# 328_ch340g_testas.net
KiCad netlist of a schematic drawn in EAGLE
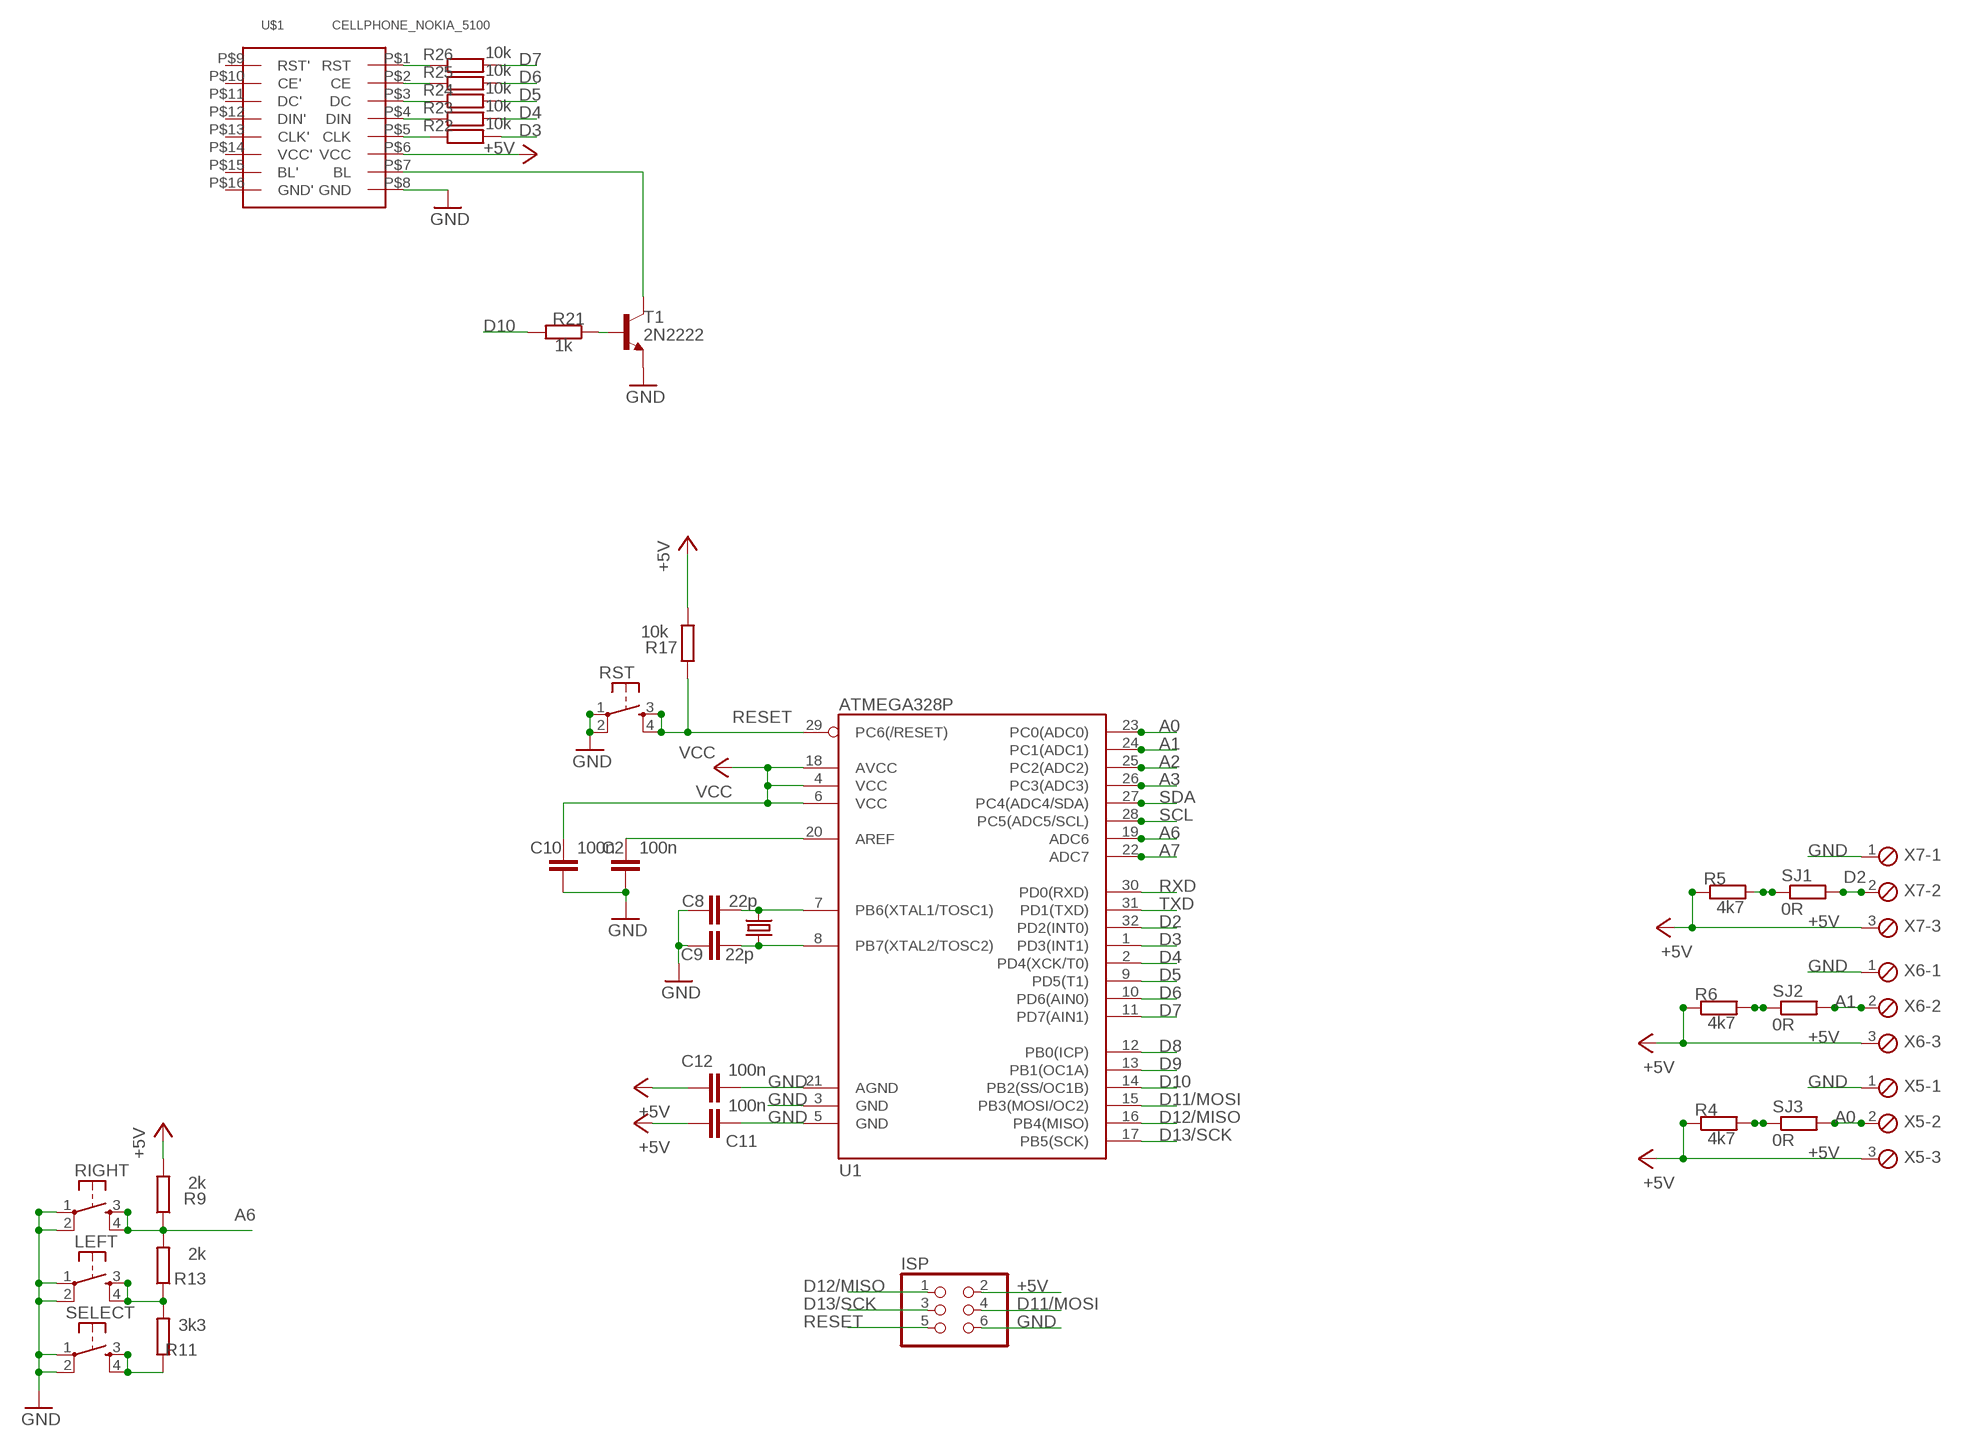
[diagram p0: schematic, sheet 1]

(export (version "E")
  (design (tool "Eeschema 10.0.6"))
  (components
    (comp (ref "C2")
      (value "100n")
      (footprint "eagle-import:C0805")
      (libsource (lib "eagle-import") (part "C-EUC0805"))
    )
    (comp (ref "C8")
      (value "22p")
      (footprint "eagle-import:C0805")
      (libsource (lib "eagle-import") (part "C-EUC0805"))
    )
    (comp (ref "C9")
      (value "22p")
      (footprint "eagle-import:C0805")
      (libsource (lib "eagle-import") (part "C-EUC0805"))
    )
    (comp (ref "C10")
      (value "100n")
      (footprint "eagle-import:C0805")
      (libsource (lib "eagle-import") (part "C-EUC0805"))
    )
    (comp (ref "C11")
      (value "100n")
      (footprint "eagle-import:C0805")
      (libsource (lib "eagle-import") (part "C-EUC0805"))
    )
    (comp (ref "C12")
      (value "100n")
      (footprint "eagle-import:C0805")
      (libsource (lib "eagle-import") (part "C-EUC0805"))
    )
    (comp (ref "ISP")
      (value "PINHD-2X3")
      (footprint "eagle-import:2X03")
      (libsource (lib "eagle-import") (part "PINHD-2X3"))
    )
    (comp (ref "LEFT")
      (value "TAC_SWITCHPTH")
      (footprint "eagle-import:TACTILE-PTH")
      (libsource (lib "eagle-import") (part "TAC_SWITCHPTH"))
    )
    (comp (ref "R4")
      (value "4k7")
      (footprint "eagle-import:R0805")
      (libsource (lib "eagle-import") (part "R-EU_R0805"))
    )
    (comp (ref "R5")
      (value "4k7")
      (footprint "eagle-import:R0805")
      (libsource (lib "eagle-import") (part "R-EU_R0805"))
    )
    (comp (ref "R6")
      (value "4k7")
      (footprint "eagle-import:R0805")
      (libsource (lib "eagle-import") (part "R-EU_R0805"))
    )
    (comp (ref "R9")
      (value "2k")
      (footprint "eagle-import:R0805")
      (libsource (lib "eagle-import") (part "R-EU_R0805"))
    )
    (comp (ref "R11")
      (value "3k3")
      (footprint "eagle-import:R0805")
      (libsource (lib "eagle-import") (part "R-EU_R0805"))
    )
    (comp (ref "R13")
      (value "2k")
      (footprint "eagle-import:R0805")
      (libsource (lib "eagle-import") (part "R-EU_R0805"))
    )
    (comp (ref "R17")
      (value "10k")
      (footprint "eagle-import:R0805")
      (libsource (lib "eagle-import") (part "R-EU_R0805"))
    )
    (comp (ref "R21")
      (value "1k")
      (footprint "eagle-import:R0805")
      (libsource (lib "eagle-import") (part "R-EU_R0805"))
    )
    (comp (ref "R22")
      (value "10k")
      (footprint "eagle-import:R0805")
      (libsource (lib "eagle-import") (part "R-EU_R0805"))
    )
    (comp (ref "R23")
      (value "10k")
      (footprint "eagle-import:R0805")
      (libsource (lib "eagle-import") (part "R-EU_R0805"))
    )
    (comp (ref "R24")
      (value "10k")
      (footprint "eagle-import:R0805")
      (libsource (lib "eagle-import") (part "R-EU_R0805"))
    )
    (comp (ref "R25")
      (value "10k")
      (footprint "eagle-import:R0805")
      (libsource (lib "eagle-import") (part "R-EU_R0805"))
    )
    (comp (ref "R26")
      (value "10k")
      (footprint "eagle-import:R0805")
      (libsource (lib "eagle-import") (part "R-EU_R0805"))
    )
    (comp (ref "RIGHT")
      (value "TAC_SWITCHPTH")
      (footprint "eagle-import:TACTILE-PTH")
      (libsource (lib "eagle-import") (part "TAC_SWITCHPTH"))
    )
    (comp (ref "RST")
      (value "TAC_SWITCHPTH")
      (footprint "eagle-import:TACTILE-PTH")
      (libsource (lib "eagle-import") (part "TAC_SWITCHPTH"))
    )
    (comp (ref "SELECT")
      (value "TAC_SWITCHPTH")
      (footprint "eagle-import:TACTILE-PTH")
      (libsource (lib "eagle-import") (part "TAC_SWITCHPTH"))
    )
    (comp (ref "SJ1")
      (value "0R")
      (footprint "eagle-import:R0402")
      (libsource (lib "eagle-import") (part "R-EU_R0402"))
    )
    (comp (ref "SJ2")
      (value "0R")
      (footprint "eagle-import:R0402")
      (libsource (lib "eagle-import") (part "R-EU_R0402"))
    )
    (comp (ref "SJ3")
      (value "0R")
      (footprint "eagle-import:R0402")
      (libsource (lib "eagle-import") (part "R-EU_R0402"))
    )
    (comp (ref "T1")
      (value "2N2222")
      (footprint "eagle-import:TO92-EBC-OVAL")
      (libsource (lib "eagle-import") (part "2N2222"))
    )
    (comp (ref "U$1")
      (value "CELLPHONE_NOKIA_5100")
      (footprint "eagle-import:CELLPHONE_NOKIA_5100_SPARKFUN")
      (libsource (lib "eagle-import") (part "CELLPHONE_NOKIA_5100"))
    )
    (comp (ref "U1")
      (value "ATMEGA328P")
      (footprint "eagle-import:TQFP32-08")
      (libsource (lib "eagle-import") (part "ATMEGA328_SMT"))
    )
    (comp (ref "X2")
      (value "16MHz")
      (footprint "eagle-import:HC49US")
      (libsource (lib "eagle-import") (part "CRYSTALHC49US"))
    )
    (comp (ref "X5")
      (value "MPT3")
      (footprint "eagle-import:3POL254")
      (libsource (lib "eagle-import") (part "MPT3"))
    )
    (comp (ref "X6")
      (value "MPT3")
      (footprint "eagle-import:3POL254")
      (libsource (lib "eagle-import") (part "MPT3"))
    )
    (comp (ref "X7")
      (value "MPT3")
      (footprint "eagle-import:3POL254")
      (libsource (lib "eagle-import") (part "MPT3"))
    )
  )
  (nets
    (net (code "1") (name "+5V") (class "Default")
      (node (ref "C11") (pin "2") (pinfunction "2_2") (pintype "passive"))
      (node (ref "C12") (pin "2") (pinfunction "2_2") (pintype "passive"))
      (node (ref "ISP") (pin "2") (pinfunction "2_2") (pintype "passive"))
      (node (ref "R17") (pin "2") (pinfunction "2_2") (pintype "passive"))
      (node (ref "R4") (pin "1") (pinfunction "1_1") (pintype "passive"))
      (node (ref "R5") (pin "1") (pinfunction "1_1") (pintype "passive"))
      (node (ref "R6") (pin "1") (pinfunction "1_1") (pintype "passive"))
      (node (ref "R9") (pin "2") (pinfunction "2_2") (pintype "passive"))
      (node (ref "U$1") (pin "P$6") (pinfunction "VCC_P$6") (pintype "bidirectional"))
      (node (ref "X5") (pin "3") (pinfunction "1_3") (pintype "passive"))
      (node (ref "X6") (pin "3") (pinfunction "1_3") (pintype "passive"))
      (node (ref "X7") (pin "3") (pinfunction "1_3") (pintype "passive"))
    )
    (net (code "2") (name "/A0") (class "Default")
      (node (ref "SJ3") (pin "2") (pinfunction "2_2") (pintype "passive"))
      (node (ref "U1") (pin "23") (pinfunction "PC0(ADC0)_23") (pintype "bidirectional"))
      (node (ref "X5") (pin "2") (pinfunction "1_2") (pintype "passive"))
    )
    (net (code "3") (name "/A1") (class "Default")
      (node (ref "SJ2") (pin "2") (pinfunction "2_2") (pintype "passive"))
      (node (ref "U1") (pin "24") (pinfunction "PC1(ADC1)_24") (pintype "bidirectional"))
      (node (ref "X6") (pin "2") (pinfunction "1_2") (pintype "passive"))
    )
    (net (code "4") (name "/A2") (class "Default")
      (node (ref "U1") (pin "25") (pinfunction "PC2(ADC2)_25") (pintype "bidirectional"))
    )
    (net (code "5") (name "/A3") (class "Default")
      (node (ref "U1") (pin "26") (pinfunction "PC3(ADC3)_26") (pintype "bidirectional"))
    )
    (net (code "6") (name "/A6") (class "Default")
      (node (ref "R13") (pin "2") (pinfunction "2_2") (pintype "passive"))
      (node (ref "R9") (pin "1") (pinfunction "1_1") (pintype "passive"))
      (node (ref "RIGHT") (pin "3") (pinfunction "3_3") (pintype "passive"))
      (node (ref "RIGHT") (pin "4") (pinfunction "4_4") (pintype "passive"))
      (node (ref "U1") (pin "19") (pinfunction "ADC6_19") (pintype "bidirectional"))
    )
    (net (code "7") (name "/A7") (class "Default")
      (node (ref "U1") (pin "22") (pinfunction "ADC7_22") (pintype "bidirectional"))
    )
    (net (code "8") (name "/D2") (class "Default")
      (node (ref "SJ1") (pin "2") (pinfunction "2_2") (pintype "passive"))
      (node (ref "U1") (pin "32") (pinfunction "PD2(INT0)_32") (pintype "bidirectional"))
      (node (ref "X7") (pin "2") (pinfunction "1_2") (pintype "passive"))
    )
    (net (code "9") (name "/D3") (class "Default")
      (node (ref "R22") (pin "2") (pinfunction "2_2") (pintype "passive"))
      (node (ref "U1") (pin "1") (pinfunction "PD3(INT1)_1") (pintype "bidirectional"))
    )
    (net (code "10") (name "/D4") (class "Default")
      (node (ref "R23") (pin "2") (pinfunction "2_2") (pintype "passive"))
      (node (ref "U1") (pin "2") (pinfunction "PD4(XCK/T0)_2") (pintype "bidirectional"))
    )
    (net (code "11") (name "/D5") (class "Default")
      (node (ref "R24") (pin "2") (pinfunction "2_2") (pintype "passive"))
      (node (ref "U1") (pin "9") (pinfunction "PD5(T1)_9") (pintype "bidirectional"))
    )
    (net (code "12") (name "/D6") (class "Default")
      (node (ref "R25") (pin "2") (pinfunction "2_2") (pintype "passive"))
      (node (ref "U1") (pin "10") (pinfunction "PD6(AIN0)_10") (pintype "bidirectional"))
    )
    (net (code "13") (name "/D7") (class "Default")
      (node (ref "R26") (pin "2") (pinfunction "2_2") (pintype "passive"))
      (node (ref "U1") (pin "11") (pinfunction "PD7(AIN1)_11") (pintype "bidirectional"))
    )
    (net (code "14") (name "/D8") (class "Default")
      (node (ref "U1") (pin "12") (pinfunction "PB0(ICP)_12") (pintype "bidirectional"))
    )
    (net (code "15") (name "/D9") (class "Default")
      (node (ref "U1") (pin "13") (pinfunction "PB1(OC1A)_13") (pintype "bidirectional"))
    )
    (net (code "16") (name "/D10") (class "Default")
      (node (ref "R21") (pin "2") (pinfunction "2_2") (pintype "passive"))
      (node (ref "U1") (pin "14") (pinfunction "PB2(SS/OC1B)_14") (pintype "bidirectional"))
    )
    (net (code "17") (name "/D11{slash}MOSI") (class "Default")
      (node (ref "ISP") (pin "4") (pinfunction "4_4") (pintype "passive"))
      (node (ref "U1") (pin "15") (pinfunction "PB3(MOSI/OC2)_15") (pintype "bidirectional"))
    )
    (net (code "18") (name "/D12{slash}MISO") (class "Default")
      (node (ref "ISP") (pin "1") (pinfunction "1_1") (pintype "passive"))
      (node (ref "U1") (pin "16") (pinfunction "PB4(MISO)_16") (pintype "bidirectional"))
    )
    (net (code "19") (name "/D13{slash}SCK") (class "Default")
      (node (ref "ISP") (pin "3") (pinfunction "3_3") (pintype "passive"))
      (node (ref "U1") (pin "17") (pinfunction "PB5(SCK)_17") (pintype "bidirectional"))
    )
    (net (code "20") (name "/RESET") (class "Default")
      (node (ref "ISP") (pin "5") (pinfunction "5_5") (pintype "passive"))
      (node (ref "R17") (pin "1") (pinfunction "1_1") (pintype "passive"))
      (node (ref "RST") (pin "3") (pinfunction "3_3") (pintype "passive"))
      (node (ref "RST") (pin "4") (pinfunction "4_4") (pintype "passive"))
      (node (ref "U1") (pin "29") (pinfunction "PC6(/RESET)_29") (pintype "bidirectional"))
    )
    (net (code "21") (name "/RXD") (class "Default")
      (node (ref "U1") (pin "30") (pinfunction "PD0(RXD)_30") (pintype "bidirectional"))
    )
    (net (code "22") (name "/SCL") (class "Default")
      (node (ref "U1") (pin "28") (pinfunction "PC5(ADC5/SCL)_28") (pintype "bidirectional"))
    )
    (net (code "23") (name "/SDA") (class "Default")
      (node (ref "U1") (pin "27") (pinfunction "PC4(ADC4/SDA)_27") (pintype "bidirectional"))
    )
    (net (code "24") (name "/TXD") (class "Default")
      (node (ref "U1") (pin "31") (pinfunction "PD1(TXD)_31") (pintype "bidirectional"))
    )
    (net (code "25") (name "GND") (class "Default")
      (node (ref "C10") (pin "2") (pinfunction "2_2") (pintype "passive"))
      (node (ref "C11") (pin "1") (pinfunction "1_1") (pintype "passive"))
      (node (ref "C12") (pin "1") (pinfunction "1_1") (pintype "passive"))
      (node (ref "C2") (pin "2") (pinfunction "2_2") (pintype "passive"))
      (node (ref "C8") (pin "1") (pinfunction "1_1") (pintype "passive"))
      (node (ref "C9") (pin "1") (pinfunction "1_1") (pintype "passive"))
      (node (ref "ISP") (pin "6") (pinfunction "6_6") (pintype "passive"))
      (node (ref "LEFT") (pin "1") (pinfunction "1_1") (pintype "passive"))
      (node (ref "LEFT") (pin "2") (pinfunction "2_2") (pintype "passive"))
      (node (ref "RIGHT") (pin "1") (pinfunction "1_1") (pintype "passive"))
      (node (ref "RIGHT") (pin "2") (pinfunction "2_2") (pintype "passive"))
      (node (ref "RST") (pin "1") (pinfunction "1_1") (pintype "passive"))
      (node (ref "RST") (pin "2") (pinfunction "2_2") (pintype "passive"))
      (node (ref "SELECT") (pin "1") (pinfunction "1_1") (pintype "passive"))
      (node (ref "SELECT") (pin "2") (pinfunction "2_2") (pintype "passive"))
      (node (ref "T1") (pin "E") (pinfunction "E_E") (pintype "passive"))
      (node (ref "U$1") (pin "P$8") (pinfunction "GND_P$8") (pintype "bidirectional"))
      (node (ref "U1") (pin "21") (pinfunction "AGND_21") (pintype "bidirectional"))
      (node (ref "U1") (pin "3") (pinfunction "GND_3") (pintype "bidirectional"))
      (node (ref "U1") (pin "5") (pinfunction "GND_5") (pintype "bidirectional"))
      (node (ref "X5") (pin "1") (pinfunction "1_1") (pintype "passive"))
      (node (ref "X6") (pin "1") (pinfunction "1_1") (pintype "passive"))
      (node (ref "X7") (pin "1") (pinfunction "1_1") (pintype "passive"))
    )
    (net (code "26") (name "Net-(LEFT-Pad3)") (class "Default")
      (node (ref "LEFT") (pin "3") (pinfunction "3_3") (pintype "passive"))
      (node (ref "LEFT") (pin "4") (pinfunction "4_4") (pintype "passive"))
      (node (ref "R11") (pin "2") (pinfunction "2_2") (pintype "passive"))
      (node (ref "R13") (pin "1") (pinfunction "1_1") (pintype "passive"))
    )
    (net (code "27") (name "Net-(R4-Pad2)") (class "Default")
      (node (ref "R4") (pin "2") (pinfunction "2_2") (pintype "passive"))
      (node (ref "SJ3") (pin "1") (pinfunction "1_1") (pintype "passive"))
    )
    (net (code "28") (name "Net-(R5-Pad2)") (class "Default")
      (node (ref "R5") (pin "2") (pinfunction "2_2") (pintype "passive"))
      (node (ref "SJ1") (pin "1") (pinfunction "1_1") (pintype "passive"))
    )
    (net (code "29") (name "Net-(R6-Pad2)") (class "Default")
      (node (ref "R6") (pin "2") (pinfunction "2_2") (pintype "passive"))
      (node (ref "SJ2") (pin "1") (pinfunction "1_1") (pintype "passive"))
    )
    (net (code "30") (name "Net-(R11-Pad1)") (class "Default")
      (node (ref "R11") (pin "1") (pinfunction "1_1") (pintype "passive"))
      (node (ref "SELECT") (pin "3") (pinfunction "3_3") (pintype "passive"))
      (node (ref "SELECT") (pin "4") (pinfunction "4_4") (pintype "passive"))
    )
    (net (code "31") (name "Net-(R21-Pad1)") (class "Default")
      (node (ref "R21") (pin "1") (pinfunction "1_1") (pintype "passive"))
      (node (ref "T1") (pin "B") (pinfunction "B_B") (pintype "passive"))
    )
    (net (code "32") (name "Net-(U$1-BL)") (class "Default")
      (node (ref "T1") (pin "C") (pinfunction "C_C") (pintype "passive"))
      (node (ref "U$1") (pin "P$7") (pinfunction "BL_P$7") (pintype "bidirectional"))
    )
    (net (code "33") (name "Net-(U$1-CE)") (class "Default")
      (node (ref "R25") (pin "1") (pinfunction "1_1") (pintype "passive"))
      (node (ref "U$1") (pin "P$2") (pinfunction "CE_P$2") (pintype "bidirectional"))
    )
    (net (code "34") (name "Net-(U$1-CLK)") (class "Default")
      (node (ref "R22") (pin "1") (pinfunction "1_1") (pintype "passive"))
      (node (ref "U$1") (pin "P$5") (pinfunction "CLK_P$5") (pintype "bidirectional"))
    )
    (net (code "35") (name "Net-(U$1-DC)") (class "Default")
      (node (ref "R24") (pin "1") (pinfunction "1_1") (pintype "passive"))
      (node (ref "U$1") (pin "P$3") (pinfunction "DC_P$3") (pintype "bidirectional"))
    )
    (net (code "36") (name "Net-(U$1-DIN)") (class "Default")
      (node (ref "R23") (pin "1") (pinfunction "1_1") (pintype "passive"))
      (node (ref "U$1") (pin "P$4") (pinfunction "DIN_P$4") (pintype "bidirectional"))
    )
    (net (code "37") (name "Net-(U$1-RST)") (class "Default")
      (node (ref "R26") (pin "1") (pinfunction "1_1") (pintype "passive"))
      (node (ref "U$1") (pin "P$1") (pinfunction "RST_P$1") (pintype "bidirectional"))
    )
    (net (code "38") (name "Net-(U1-AREF)") (class "Default")
      (node (ref "C2") (pin "1") (pinfunction "1_1") (pintype "passive"))
      (node (ref "U1") (pin "20") (pinfunction "AREF_20") (pintype "bidirectional"))
    )
    (net (code "39") (name "Net-(U1-PB6(XTAL1{slash}TOSC1))") (class "Default")
      (node (ref "C8") (pin "2") (pinfunction "2_2") (pintype "passive"))
      (node (ref "U1") (pin "7") (pinfunction "PB6(XTAL1/TOSC1)_7") (pintype "bidirectional"))
      (node (ref "X2") (pin "2") (pinfunction "2_2") (pintype "passive"))
    )
    (net (code "40") (name "Net-(U1-PB7(XTAL2{slash}TOSC2))") (class "Default")
      (node (ref "C9") (pin "2") (pinfunction "2_2") (pintype "passive"))
      (node (ref "U1") (pin "8") (pinfunction "PB7(XTAL2/TOSC2)_8") (pintype "bidirectional"))
      (node (ref "X2") (pin "1") (pinfunction "1_1") (pintype "passive"))
    )
    (net (code "41") (name "VCC") (class "Default")
      (node (ref "C10") (pin "1") (pinfunction "1_1") (pintype "passive"))
      (node (ref "U1") (pin "18") (pinfunction "AVCC_18") (pintype "bidirectional"))
      (node (ref "U1") (pin "4") (pinfunction "VCC_4") (pintype "bidirectional"))
      (node (ref "U1") (pin "6") (pinfunction "VCC_6") (pintype "bidirectional"))
    )
    (net (code "42") (name "unconnected-(U$1-BL'-PadP$15)") (class "Default")
      (node (ref "U$1") (pin "P$15") (pinfunction "BL'_P$15") (pintype "bidirectional"))
    )
    (net (code "43") (name "unconnected-(U$1-CE'-PadP$10)") (class "Default")
      (node (ref "U$1") (pin "P$10") (pinfunction "CE'_P$10") (pintype "bidirectional"))
    )
    (net (code "44") (name "unconnected-(U$1-CLK'-PadP$13)") (class "Default")
      (node (ref "U$1") (pin "P$13") (pinfunction "CLK'_P$13") (pintype "bidirectional"))
    )
    (net (code "45") (name "unconnected-(U$1-DC'-PadP$11)") (class "Default")
      (node (ref "U$1") (pin "P$11") (pinfunction "DC'_P$11") (pintype "bidirectional"))
    )
    (net (code "46") (name "unconnected-(U$1-DIN'-PadP$12)") (class "Default")
      (node (ref "U$1") (pin "P$12") (pinfunction "DIN'_P$12") (pintype "bidirectional"))
    )
    (net (code "47") (name "unconnected-(U$1-GND'-PadP$16)") (class "Default")
      (node (ref "U$1") (pin "P$16") (pinfunction "GND'_P$16") (pintype "bidirectional"))
    )
    (net (code "48") (name "unconnected-(U$1-RST'-PadP$9)") (class "Default")
      (node (ref "U$1") (pin "P$9") (pinfunction "RST'_P$9") (pintype "bidirectional"))
    )
    (net (code "49") (name "unconnected-(U$1-VCC'-PadP$14)") (class "Default")
      (node (ref "U$1") (pin "P$14") (pinfunction "VCC'_P$14") (pintype "bidirectional"))
    )
  )
)
